# QCopterFC_SD_Sch.net
KiCad netlist of a schematic drawn in Altium Designer
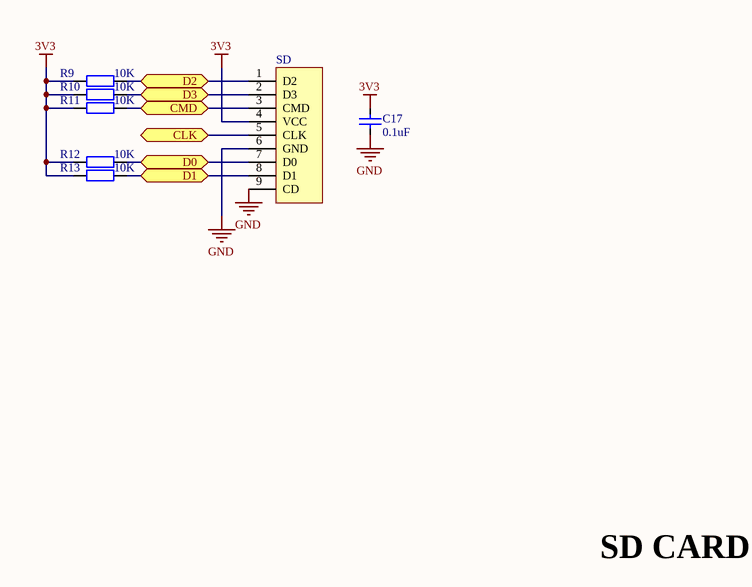
[diagram p0: QCopterFC_SD_Sch.SchDoc]

(export (version "E")
  (design (tool "Eeschema 10.0.6"))
  (components
    (comp (ref "C17")
      (value "0.1uF")
      (footprint "PCB_Passive:CAP_0603")
      (description "Capacitor")
      (fields (field (name "Comment") "Cap_0603"))
      (libsource (lib "SCH_Passive") (part "Cap_0603"))
    )
    (comp (ref "R9")
      (value "10K")
      (footprint "PCB_Passive:RES_0603")
      (description "Resistor")
      (fields (field (name "Comment") "Res_0603"))
      (libsource (lib "SCH_Passive") (part "Res_0603"))
    )
    (comp (ref "R10")
      (value "10K")
      (footprint "PCB_Passive:RES_0603")
      (description "Resistor")
      (fields (field (name "Comment") "Res_0603"))
      (libsource (lib "SCH_Passive") (part "Res_0603"))
    )
    (comp (ref "R11")
      (value "10K")
      (footprint "PCB_Passive:RES_0603")
      (description "Resistor")
      (fields (field (name "Comment") "Res_0603"))
      (libsource (lib "SCH_Passive") (part "Res_0603"))
    )
    (comp (ref "R12")
      (value "10K")
      (footprint "PCB_Passive:RES_0603")
      (description "Resistor")
      (fields (field (name "Comment") "Res_0603"))
      (libsource (lib "SCH_Passive") (part "Res_0603"))
    )
    (comp (ref "R13")
      (value "10K")
      (footprint "PCB_Passive:RES_0603")
      (description "Resistor")
      (fields (field (name "Comment") "Res_0603"))
      (libsource (lib "SCH_Passive") (part "Res_0603"))
    )
    (comp (ref "SD")
      (value "SD_Card_TF")
      (footprint "PCB_SDCard:SD_Card_TF")
      (description "SD")
      (libsource (lib "SCH_SDCard") (part "SD_Card_TF"))
    )
  )
  (nets
    (net (code "1") (name "/CLK") (class "Default")
      (node (ref "SD") (pin "5") (pinfunction "CLK_5") (pintype "passive"))
    )
    (net (code "2") (name "/CMD") (class "Default")
      (node (ref "R11") (pin "2") (pinfunction "2_2") (pintype "passive"))
      (node (ref "SD") (pin "3") (pinfunction "CMD_3") (pintype "passive"))
    )
    (net (code "3") (name "/D0") (class "Default")
      (node (ref "R12") (pin "2") (pinfunction "2_2") (pintype "passive"))
      (node (ref "SD") (pin "7") (pinfunction "D0_7") (pintype "passive"))
    )
    (net (code "4") (name "/D1") (class "Default")
      (node (ref "R13") (pin "2") (pinfunction "2_2") (pintype "passive"))
      (node (ref "SD") (pin "8") (pinfunction "D1_8") (pintype "passive"))
    )
    (net (code "5") (name "/D2") (class "Default")
      (node (ref "R9") (pin "2") (pinfunction "2_2") (pintype "passive"))
      (node (ref "SD") (pin "1") (pinfunction "D2_1") (pintype "passive"))
    )
    (net (code "6") (name "/D3") (class "Default")
      (node (ref "R10") (pin "2") (pinfunction "2_2") (pintype "passive"))
      (node (ref "SD") (pin "2") (pinfunction "D3_2") (pintype "passive"))
    )
    (net (code "8") (name "3V3") (class "Default")
      (node (ref "C17") (pin "2") (pinfunction "2_2") (pintype "passive"))
      (node (ref "R10") (pin "1") (pinfunction "1_1") (pintype "passive"))
      (node (ref "R11") (pin "1") (pinfunction "1_1") (pintype "passive"))
      (node (ref "R12") (pin "1") (pinfunction "1_1") (pintype "passive"))
      (node (ref "R13") (pin "1") (pinfunction "1_1") (pintype "passive"))
      (node (ref "R9") (pin "1") (pinfunction "1_1") (pintype "passive"))
      (node (ref "SD") (pin "4") (pinfunction "VCC_4") (pintype "passive"))
    )
    (net (code "9") (name "GND") (class "Default")
      (node (ref "C17") (pin "1") (pinfunction "1_1") (pintype "passive"))
      (node (ref "SD") (pin "6") (pinfunction "GND_6") (pintype "passive"))
      (node (ref "SD") (pin "9") (pinfunction "CD_9") (pintype "passive"))
    )
  )
)
